# Schematic_IF_filter.net
KiCad netlist of a schematic drawn in Altium Designer
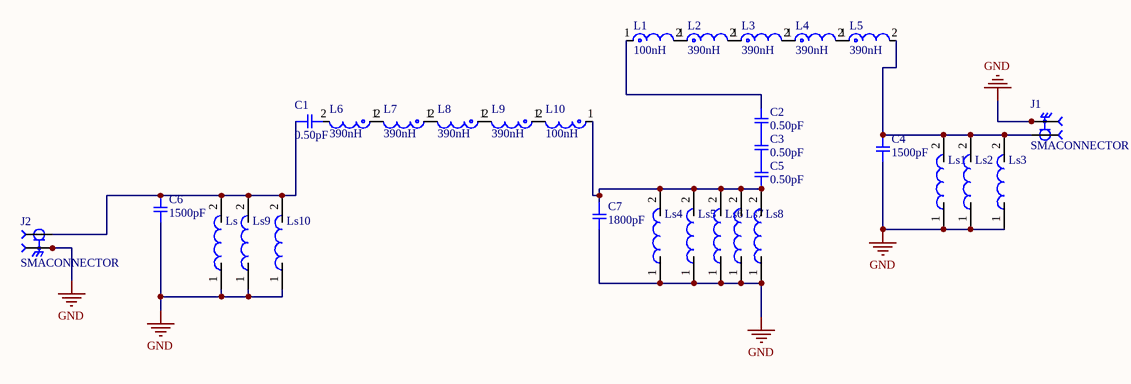
[diagram p0: Schematic_IF_filter.SchDoc]

(export (version "E")
  (design (tool "Eeschema 10.0.6"))
  (components
    (comp (ref "C1")
      (value "0.50pF")
      (footprint "SMD-0402C")
      (description "CAP CER 0.5PF 100V NP0 0402")
      (fields
        (field (name "DIGI-KEY PART NUMBER") "490-7274-1-ND")
        (field (name "PART NUMBER") "GRM1555C2AR50BA01D")
      )
      (libsource (lib "capacitor_murata_0402") (part "GRM1555C2AR50BA01D"))
    )
    (comp (ref "C2")
      (value "0.50pF")
      (footprint "SMD-0402C")
      (description "CAP CER 0.5PF 100V NP0 0402")
      (fields
        (field (name "DIGI-KEY PART NUMBER") "490-7274-1-ND")
        (field (name "PART NUMBER") "GRM1555C2AR50BA01D")
      )
      (libsource (lib "capacitor_murata_0402") (part "GRM1555C2AR50BA01D"))
    )
    (comp (ref "C3")
      (value "0.50pF")
      (footprint "SMD-0402C")
      (description "CAP CER 0.5PF 100V NP0 0402")
      (fields
        (field (name "DIGI-KEY PART NUMBER") "490-7274-1-ND")
        (field (name "PART NUMBER") "GRM1555C2AR50BA01D")
      )
      (libsource (lib "capacitor_murata_0402") (part "GRM1555C2AR50BA01D"))
    )
    (comp (ref "C4")
      (value "1500pF")
      (footprint "SMD-0603C")
      (description "CAP CER 1500PF 50V NP0 0603")
      (fields
        (field (name "DIGI-KEY PART NUMBER") "490-4967-1-ND")
        (field (name "PART NUMBER") "GCM1885C1H152JA16D")
      )
      (libsource (lib "capacitor_murata_0603") (part "GCM1885C1H152JA16D"))
    )
    (comp (ref "C5")
      (value "0.50pF")
      (footprint "SMD-0402C")
      (description "CAP CER 0.5PF 100V NP0 0402")
      (fields
        (field (name "DIGI-KEY PART NUMBER") "490-7274-1-ND")
        (field (name "PART NUMBER") "GRM1555C2AR50BA01D")
      )
      (libsource (lib "capacitor_murata_0402") (part "GRM1555C2AR50BA01D"))
    )
    (comp (ref "C6")
      (value "1500pF")
      (footprint "SMD-0603C")
      (description "CAP CER 1500PF 50V NP0 0603")
      (fields
        (field (name "DIGI-KEY PART NUMBER") "490-4967-1-ND")
        (field (name "PART NUMBER") "GCM1885C1H152JA16D")
      )
      (libsource (lib "capacitor_murata_0603") (part "GCM1885C1H152JA16D"))
    )
    (comp (ref "C7")
      (value "1800pF")
      (footprint "SMD-0603C")
      (description "CAP CER 1800PF 50V NP0 0603")
      (fields
        (field (name "DIGI-KEY PART NUMBER") "490-8004-1-ND")
        (field (name "PART NUMBER") "GCM1885C1H182JA16D")
      )
      (libsource (lib "capacitor_murata_0603") (part "GCM1885C1H182JA16D"))
    )
    (comp (ref "J1")
      (value "SMACONNECTOR")
      (footprint "LPRS_SMACONNECTOR")
      (description "SMA female RF coaxial connector for SMA male RF antennas.")
      (libsource (lib "SMACONNECTOR") (part "SMACONNECTOR"))
    )
    (comp (ref "J2")
      (value "SMACONNECTOR")
      (footprint "LPRS_SMACONNECTOR")
      (description "SMA female RF coaxial connector for SMA male RF antennas.")
      (libsource (lib "SMACONNECTOR") (part "SMACONNECTOR"))
    )
    (comp (ref "L1")
      (value "100nH")
      (footprint "FP-LQG18HH_00-MFG")
      (description "Multilayer type RF Inductor 1.8nH ±0.3nH 0.1Ω 1100mA 0603")
      (libsource (lib "Altium Content Vault") (part "4cc4b267dca4c8e51f7102f422741d8"))
    )
    (comp (ref "L2")
      (value "390nH")
      (footprint "FP-LQG18HH_00-MFG")
      (description "Multilayer type RF Inductor 1.8nH ±0.3nH 0.1Ω 1100mA 0603")
      (libsource (lib "Altium Content Vault") (part "4cc4b267dca4c8e51f7102f422741d8"))
    )
    (comp (ref "L3")
      (value "390nH")
      (footprint "FP-LQG18HH_00-MFG")
      (description "Multilayer type RF Inductor 1.8nH ±0.3nH 0.1Ω 1100mA 0603")
      (libsource (lib "Altium Content Vault") (part "4cc4b267dca4c8e51f7102f422741d8"))
    )
    (comp (ref "L4")
      (value "390nH")
      (footprint "FP-LQG18HH_00-MFG")
      (description "Multilayer type RF Inductor 1.8nH ±0.3nH 0.1Ω 1100mA 0603")
      (libsource (lib "Altium Content Vault") (part "4cc4b267dca4c8e51f7102f422741d8"))
    )
    (comp (ref "L5")
      (value "390nH")
      (footprint "FP-LQG18HH_00-MFG")
      (description "Multilayer type RF Inductor 1.8nH ±0.3nH 0.1Ω 1100mA 0603")
      (libsource (lib "Altium Content Vault") (part "4cc4b267dca4c8e51f7102f422741d8"))
    )
    (comp (ref "L6")
      (value "390nH")
      (footprint "FP-LQG18HH_00-MFG")
      (description "Multilayer type RF Inductor 1.8nH ±0.3nH 0.1Ω 1100mA 0603")
      (libsource (lib "Altium Content Vault") (part "4cc4b267dca4c8e51f7102f422741d8"))
    )
    (comp (ref "L7")
      (value "390nH")
      (footprint "FP-LQG18HH_00-MFG")
      (description "Multilayer type RF Inductor 1.8nH ±0.3nH 0.1Ω 1100mA 0603")
      (libsource (lib "Altium Content Vault") (part "4cc4b267dca4c8e51f7102f422741d8"))
    )
    (comp (ref "L8")
      (value "390nH")
      (footprint "FP-LQG18HH_00-MFG")
      (description "Multilayer type RF Inductor 1.8nH ±0.3nH 0.1Ω 1100mA 0603")
      (libsource (lib "Altium Content Vault") (part "4cc4b267dca4c8e51f7102f422741d8"))
    )
    (comp (ref "L9")
      (value "390nH")
      (footprint "FP-LQG18HH_00-MFG")
      (description "Multilayer type RF Inductor 1.8nH ±0.3nH 0.1Ω 1100mA 0603")
      (libsource (lib "Altium Content Vault") (part "4cc4b267dca4c8e51f7102f422741d8"))
    )
    (comp (ref "L10")
      (value "100nH")
      (footprint "FP-LQG18HH_00-MFG")
      (description "Multilayer type RF Inductor 1.8nH ±0.3nH 0.1Ω 1100mA 0603")
      (libsource (lib "Altium Content Vault") (part "4cc4b267dca4c8e51f7102f422741d8"))
    )
    (comp (ref "Ls")
      (value "0302cs_Coil")
      (footprint "0302CS SERIES")
      (libsource (lib "CoilLib") (part "0302cs_Coil"))
    )
    (comp (ref "Ls1")
      (value "0302cs_Coil")
      (footprint "0302CS SERIES")
      (libsource (lib "CoilLib") (part "0302cs_Coil"))
    )
    (comp (ref "Ls2")
      (value "0302cs_Coil")
      (footprint "0302CS SERIES")
      (libsource (lib "CoilLib") (part "0302cs_Coil"))
    )
    (comp (ref "Ls3")
      (value "0302cs_Coil")
      (footprint "0302CS SERIES")
      (libsource (lib "CoilLib") (part "0302cs_Coil"))
    )
    (comp (ref "Ls4")
      (value "0302cs_Coil")
      (footprint "0302CS SERIES")
      (libsource (lib "CoilLib") (part "0302cs_Coil"))
    )
    (comp (ref "Ls5")
      (value "0302cs_Coil")
      (footprint "0302CS SERIES")
      (libsource (lib "CoilLib") (part "0302cs_Coil"))
    )
    (comp (ref "Ls6")
      (value "0302cs_Coil")
      (footprint "0302CS SERIES")
      (libsource (lib "CoilLib") (part "0302cs_Coil"))
    )
    (comp (ref "Ls7")
      (value "0302cs_Coil")
      (footprint "0302CS SERIES")
      (libsource (lib "CoilLib") (part "0302cs_Coil"))
    )
    (comp (ref "Ls8")
      (value "0302cs_Coil")
      (footprint "0302CS SERIES")
      (libsource (lib "CoilLib") (part "0302cs_Coil"))
    )
    (comp (ref "Ls9")
      (value "0302cs_Coil")
      (footprint "0302CS SERIES")
      (libsource (lib "CoilLib") (part "0302cs_Coil"))
    )
    (comp (ref "Ls10")
      (value "0302cs_Coil")
      (footprint "0302CS SERIES")
      (libsource (lib "CoilLib") (part "0302cs_Coil"))
    )
  )
  (nets
    (net (code "1") (name "GND") (class "Default")
      (node (ref "C4") (pin "2") (pinfunction "2_2") (pintype "passive"))
      (node (ref "C6") (pin "2") (pinfunction "2_2") (pintype "passive"))
      (node (ref "C7") (pin "2") (pinfunction "2_2") (pintype "passive"))
      (node (ref "J1") (pin "2") (pinfunction "2_2") (pintype "passive"))
      (node (ref "J1") (pin "3") (pinfunction "2_3") (pintype "passive"))
      (node (ref "J1") (pin "4") (pinfunction "2_4") (pintype "passive"))
      (node (ref "J1") (pin "5") (pinfunction "2_5") (pintype "passive"))
      (node (ref "J2") (pin "2") (pinfunction "2_2") (pintype "passive"))
      (node (ref "J2") (pin "3") (pinfunction "2_3") (pintype "passive"))
      (node (ref "J2") (pin "4") (pinfunction "2_4") (pintype "passive"))
      (node (ref "J2") (pin "5") (pinfunction "2_5") (pintype "passive"))
      (node (ref "Ls") (pin "1") (pintype "passive"))
      (node (ref "Ls1") (pin "1") (pintype "passive"))
      (node (ref "Ls10") (pin "1") (pintype "passive"))
      (node (ref "Ls2") (pin "1") (pintype "passive"))
      (node (ref "Ls3") (pin "1") (pintype "passive"))
      (node (ref "Ls4") (pin "1") (pintype "passive"))
      (node (ref "Ls5") (pin "1") (pintype "passive"))
      (node (ref "Ls6") (pin "1") (pintype "passive"))
      (node (ref "Ls7") (pin "1") (pintype "passive"))
      (node (ref "Ls8") (pin "1") (pintype "passive"))
      (node (ref "Ls9") (pin "1") (pintype "passive"))
    )
    (net (code "2") (name "Net-(C1-Pad1)") (class "Default")
      (node (ref "C1") (pin "1") (pinfunction "1_1") (pintype "passive"))
      (node (ref "C6") (pin "1") (pinfunction "1_1") (pintype "passive"))
      (node (ref "J2") (pin "1") (pinfunction "1_1") (pintype "passive"))
      (node (ref "Ls") (pin "2") (pintype "passive"))
      (node (ref "Ls10") (pin "2") (pintype "passive"))
      (node (ref "Ls9") (pin "2") (pintype "passive"))
    )
    (net (code "3") (name "Net-(C1-Pad2)") (class "Default")
      (node (ref "C1") (pin "2") (pinfunction "2_2") (pintype "passive"))
      (node (ref "L6") (pin "2") (pinfunction "2_2") (pintype "passive"))
    )
    (net (code "4") (name "Net-(C2-Pad1)") (class "Default")
      (node (ref "C2") (pin "1") (pinfunction "1_1") (pintype "passive"))
      (node (ref "C3") (pin "2") (pinfunction "2_2") (pintype "passive"))
    )
    (net (code "5") (name "Net-(C2-Pad2)") (class "Default")
      (node (ref "C2") (pin "2") (pinfunction "2_2") (pintype "passive"))
      (node (ref "L1") (pin "1") (pinfunction "1_1") (pintype "passive"))
    )
    (net (code "6") (name "Net-(C3-Pad1)") (class "Default")
      (node (ref "C3") (pin "1") (pinfunction "1_1") (pintype "passive"))
      (node (ref "C5") (pin "2") (pinfunction "2_2") (pintype "passive"))
    )
    (net (code "7") (name "Net-(C4-Pad1)") (class "Default")
      (node (ref "C4") (pin "1") (pinfunction "1_1") (pintype "passive"))
      (node (ref "J1") (pin "1") (pinfunction "1_1") (pintype "passive"))
      (node (ref "L5") (pin "2") (pinfunction "2_2") (pintype "passive"))
      (node (ref "Ls1") (pin "2") (pintype "passive"))
      (node (ref "Ls2") (pin "2") (pintype "passive"))
      (node (ref "Ls3") (pin "2") (pintype "passive"))
    )
    (net (code "8") (name "Net-(C5-Pad1)") (class "Default")
      (node (ref "C5") (pin "1") (pinfunction "1_1") (pintype "passive"))
      (node (ref "C7") (pin "1") (pinfunction "1_1") (pintype "passive"))
      (node (ref "L10") (pin "1") (pinfunction "1_1") (pintype "passive"))
      (node (ref "Ls4") (pin "2") (pintype "passive"))
      (node (ref "Ls5") (pin "2") (pintype "passive"))
      (node (ref "Ls6") (pin "2") (pintype "passive"))
      (node (ref "Ls7") (pin "2") (pintype "passive"))
      (node (ref "Ls8") (pin "2") (pintype "passive"))
    )
    (net (code "9") (name "Net-(L1-Pad2)") (class "Default")
      (node (ref "L1") (pin "2") (pinfunction "2_2") (pintype "passive"))
      (node (ref "L2") (pin "1") (pinfunction "1_1") (pintype "passive"))
    )
    (net (code "10") (name "Net-(L2-Pad2)") (class "Default")
      (node (ref "L2") (pin "2") (pinfunction "2_2") (pintype "passive"))
      (node (ref "L3") (pin "1") (pinfunction "1_1") (pintype "passive"))
    )
    (net (code "11") (name "Net-(L3-Pad2)") (class "Default")
      (node (ref "L3") (pin "2") (pinfunction "2_2") (pintype "passive"))
      (node (ref "L4") (pin "1") (pinfunction "1_1") (pintype "passive"))
    )
    (net (code "12") (name "Net-(L4-Pad2)") (class "Default")
      (node (ref "L4") (pin "2") (pinfunction "2_2") (pintype "passive"))
      (node (ref "L5") (pin "1") (pinfunction "1_1") (pintype "passive"))
    )
    (net (code "13") (name "Net-(L6-Pad1)") (class "Default")
      (node (ref "L6") (pin "1") (pinfunction "1_1") (pintype "passive"))
      (node (ref "L7") (pin "2") (pinfunction "2_2") (pintype "passive"))
    )
    (net (code "14") (name "Net-(L7-Pad1)") (class "Default")
      (node (ref "L7") (pin "1") (pinfunction "1_1") (pintype "passive"))
      (node (ref "L8") (pin "2") (pinfunction "2_2") (pintype "passive"))
    )
    (net (code "15") (name "Net-(L8-Pad1)") (class "Default")
      (node (ref "L8") (pin "1") (pinfunction "1_1") (pintype "passive"))
      (node (ref "L9") (pin "2") (pinfunction "2_2") (pintype "passive"))
    )
    (net (code "16") (name "Net-(L10-Pad2)") (class "Default")
      (node (ref "L10") (pin "2") (pinfunction "2_2") (pintype "passive"))
      (node (ref "L9") (pin "1") (pinfunction "1_1") (pintype "passive"))
    )
  )
)
